# ESP32_with_USBC.net
KiCad netlist of a schematic drawn in Altium Designer
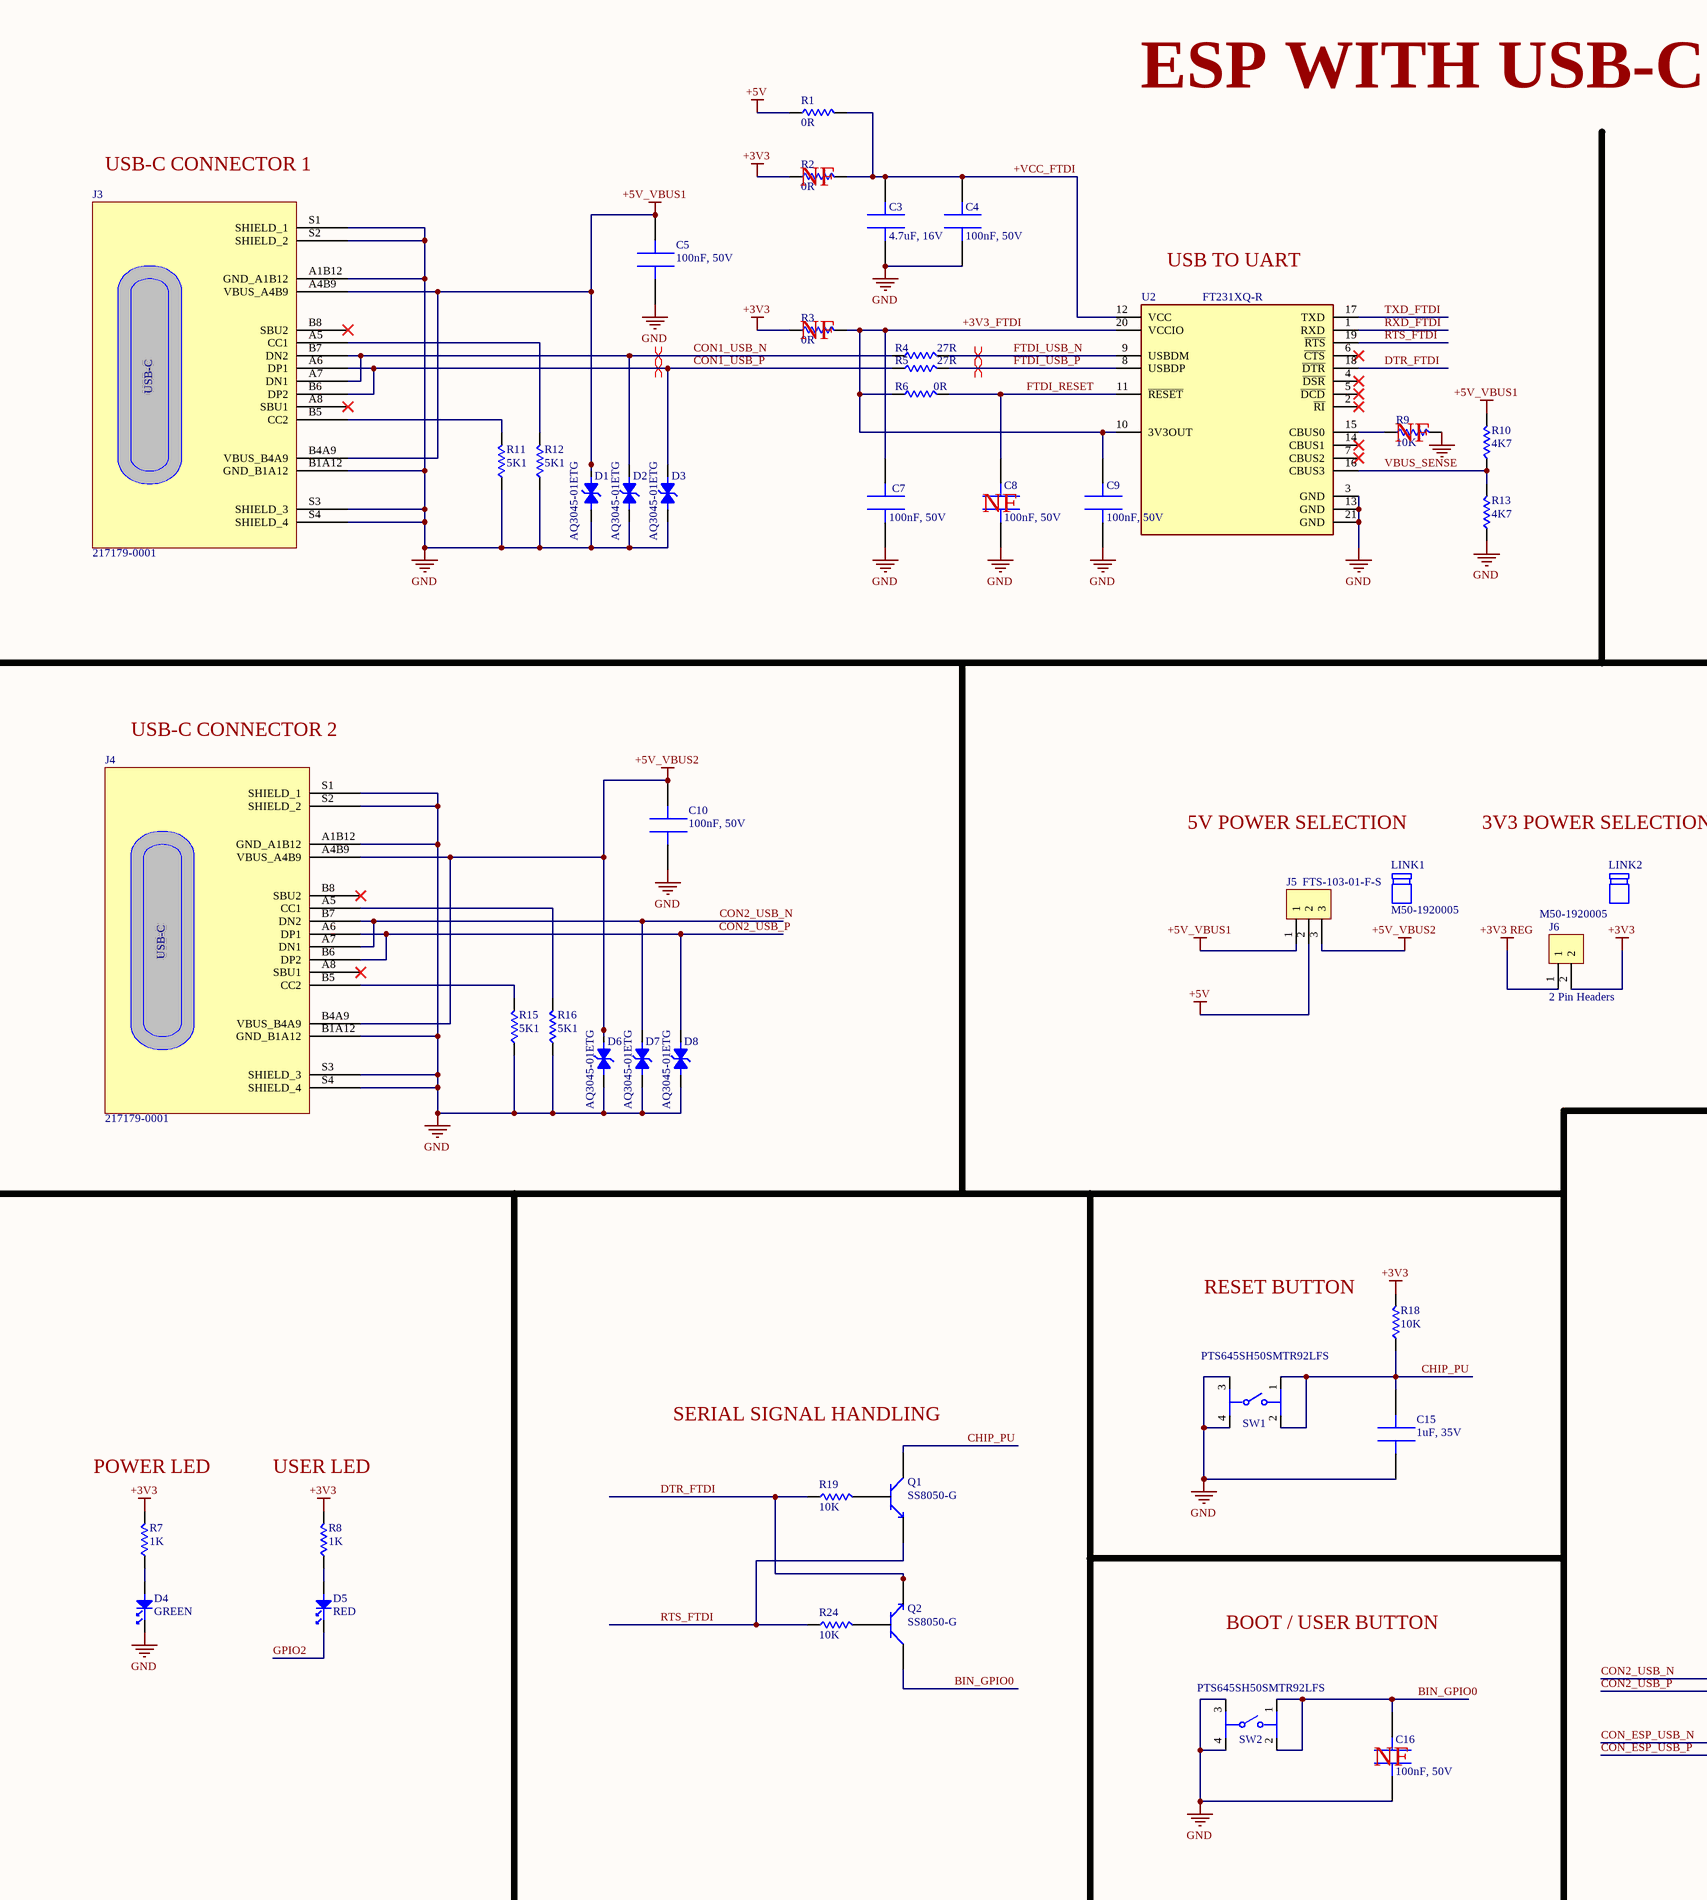
[diagram p0: ESP32 with USBC.SchDoc, left]
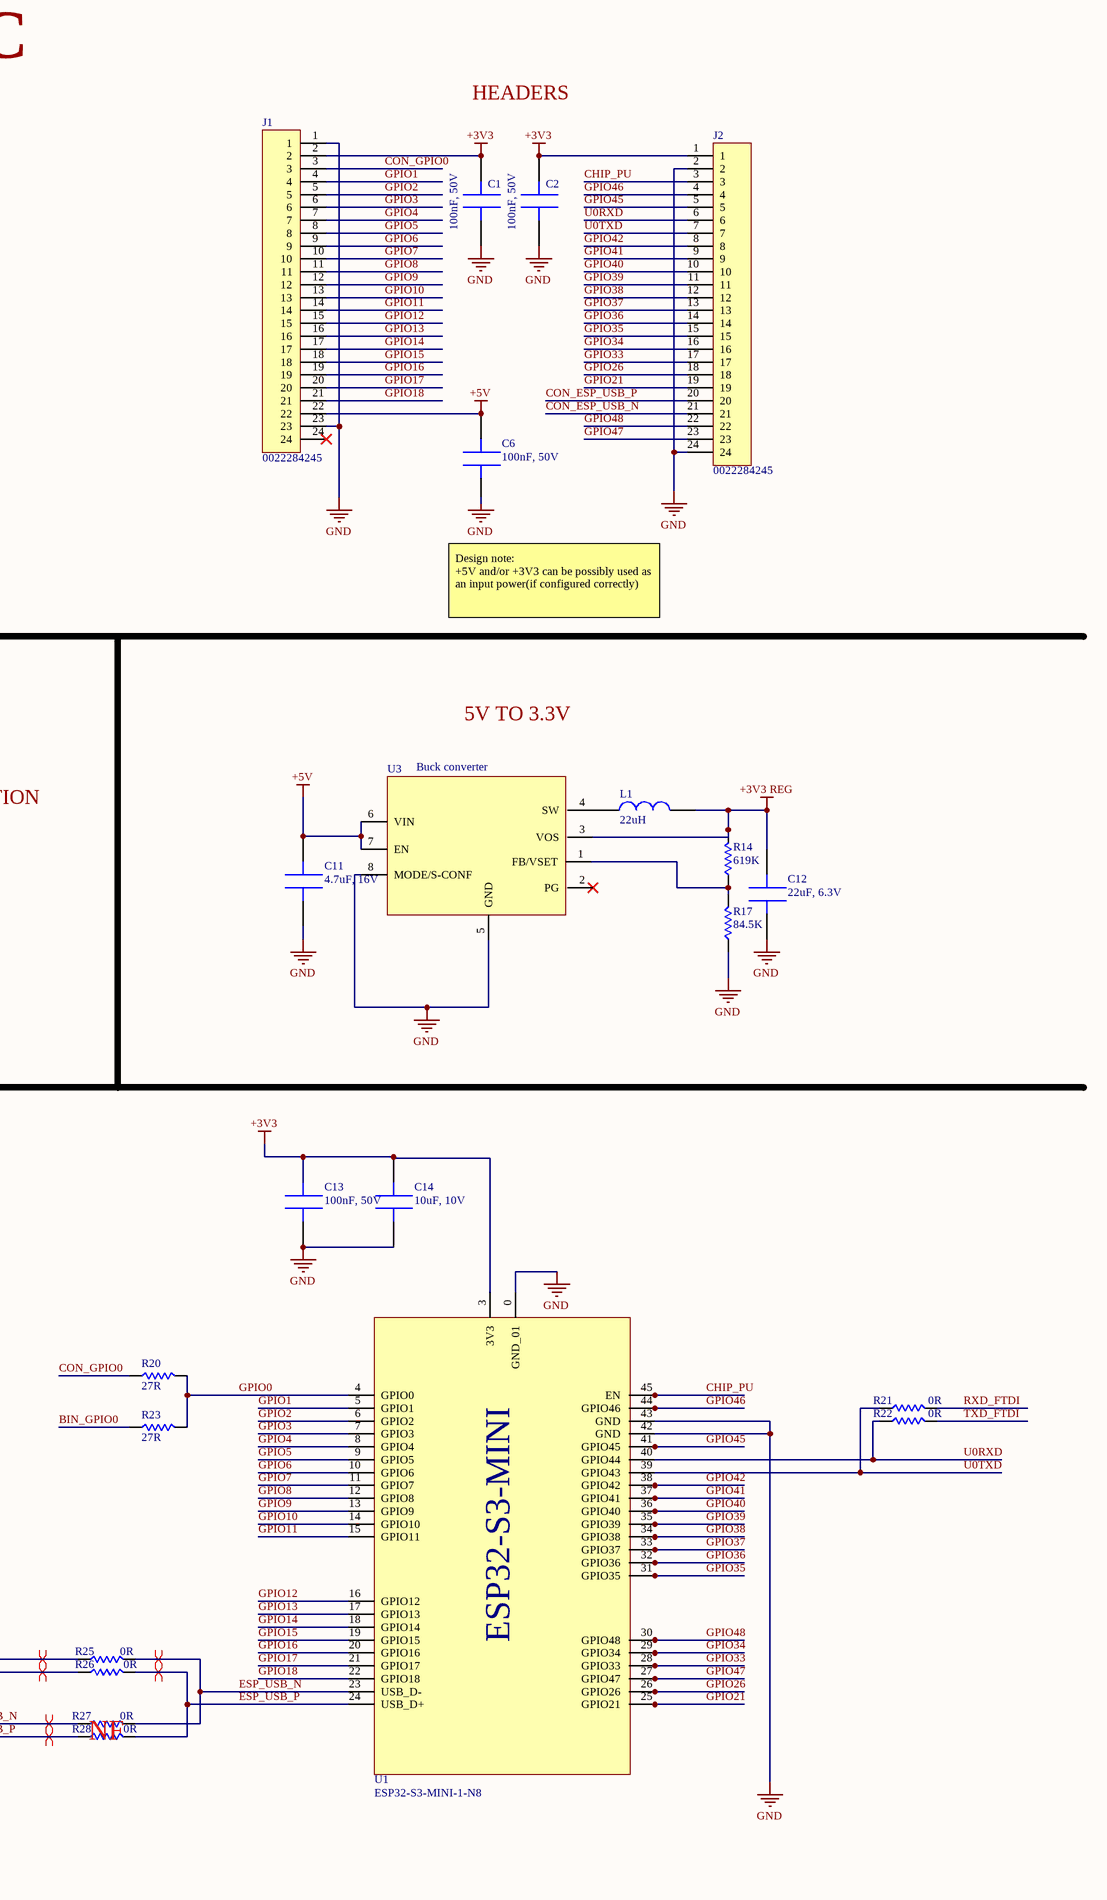
[diagram p1: ESP32 with USBC.SchDoc, right]

(export (version "E")
  (design (tool "Eeschema 10.0.6"))
  (components
    (comp (ref "C1")
      (value "100nF, 50V")
      (footprint "CAPC1005X55N")
      (description "CAP CER 0.1UF 50V X7R 0402")
      (fields
        (field (name "MANUFACTURER") "Samsung")
        (field (name "MANUFACTURER PART NUMBER") "CL05B104KB54PNC")
      )
      (libsource (lib "Schlib") (part "CL05B104KB54PNC"))
    )
    (comp (ref "C2")
      (value "100nF, 50V")
      (footprint "CAPC1005X55N")
      (description "CAP CER 0.1UF 50V X7R 0402")
      (fields
        (field (name "MANUFACTURER") "Samsung")
        (field (name "MANUFACTURER PART NUMBER") "CL05B104KB54PNC")
      )
      (libsource (lib "Schlib") (part "CL05B104KB54PNC"))
    )
    (comp (ref "C3")
      (value "4.7uF, 16V")
      (footprint "CAPC1005X55N")
      (description "16V 4.7uF X5R ±20% 0402 Multilayer Ceramic Capacitors MLCC - SMD/SMT ROHS")
      (fields
        (field (name "LCSC PART NUMBER") "C318563")
        (field (name "MANUFACTURER") "Samsung Electro-Mechanics")
      )
      (libsource (lib "Schlib") (part "CL05A475MO5NUNC"))
    )
    (comp (ref "C4")
      (value "100nF, 50V")
      (footprint "CAPC1005X55N")
      (description "CAP CER 0.1UF 50V X7R 0402")
      (fields
        (field (name "MANUFACTURER") "Samsung")
        (field (name "MANUFACTURER PART NUMBER") "CL05B104KB54PNC")
      )
      (libsource (lib "Schlib") (part "CL05B104KB54PNC"))
    )
    (comp (ref "C5")
      (value "100nF, 50V")
      (footprint "CAPC1005X55N")
      (description "CAP CER 0.1UF 50V X7R 0402")
      (fields
        (field (name "MANUFACTURER") "Samsung")
        (field (name "MANUFACTURER PART NUMBER") "CL05B104KB54PNC")
      )
      (libsource (lib "Schlib") (part "CL05B104KB54PNC"))
    )
    (comp (ref "C6")
      (value "100nF, 50V")
      (footprint "CAPC1005X55N")
      (description "CAP CER 0.1UF 50V X7R 0402")
      (fields
        (field (name "MANUFACTURER") "Samsung")
        (field (name "MANUFACTURER PART NUMBER") "CL05B104KB54PNC")
      )
      (libsource (lib "Schlib") (part "CL05B104KB54PNC"))
    )
    (comp (ref "C7")
      (value "100nF, 50V")
      (footprint "CAPC1005X55N")
      (description "CAP CER 0.1UF 50V X7R 0402")
      (fields
        (field (name "MANUFACTURER") "Samsung")
        (field (name "MANUFACTURER PART NUMBER") "CL05B104KB54PNC")
      )
      (libsource (lib "Schlib") (part "CL05B104KB54PNC"))
    )
    (comp (ref "C8")
      (value "100nF, 50V")
      (footprint "CAPC1005X55N")
      (description "CAP CER 0.1UF 50V X7R 0402")
      (fields
        (field (name "MANUFACTURER") "Samsung")
        (field (name "MANUFACTURER PART NUMBER") "CL05B104KB54PNC")
      )
      (libsource (lib "Schlib") (part "CL05B104KB54PNC"))
    )
    (comp (ref "C9")
      (value "100nF, 50V")
      (footprint "CAPC1005X55N")
      (description "CAP CER 0.1UF 50V X7R 0402")
      (fields
        (field (name "MANUFACTURER") "Samsung")
        (field (name "MANUFACTURER PART NUMBER") "CL05B104KB54PNC")
      )
      (libsource (lib "Schlib") (part "CL05B104KB54PNC"))
    )
    (comp (ref "C10")
      (value "100nF, 50V")
      (footprint "CAPC1005X55N")
      (description "CAP CER 0.1UF 50V X7R 0402")
      (fields
        (field (name "MANUFACTURER") "Samsung")
        (field (name "MANUFACTURER PART NUMBER") "CL05B104KB54PNC")
      )
      (libsource (lib "Schlib") (part "CL05B104KB54PNC"))
    )
    (comp (ref "C11")
      (value "4.7uF, 16V")
      (footprint "CAPC1005X55N")
      (description "16V 4.7uF X5R ±20% 0402 Multilayer Ceramic Capacitors MLCC - SMD/SMT ROHS")
      (fields
        (field (name "LCSC PART NUMBER") "C318563")
        (field (name "MANUFACTURER") "Samsung Electro-Mechanics")
      )
      (libsource (lib "Schlib") (part "CL05A475MO5NUNC"))
    )
    (comp (ref "C12")
      (value "22uF, 6.3V")
      (footprint "CAPC1005X55N")
      (description "6.3V 22uF X5R ±20% 0402 Multilayer Ceramic Capacitors MLCC - SMD/SMT ROHS")
      (fields
        (field (name "MANUFACTURER") "Samsung Electro-Mechanics")
        (field (name "MANUFACTURER PART NUMBER") "CL05A226MQ5QUNC")
      )
      (libsource (lib "Schlib") (part "CL05A226MQ5QUNC"))
    )
    (comp (ref "C13")
      (value "100nF, 50V")
      (footprint "CAPC1005X55N")
      (description "CAP CER 0.1UF 50V X7R 0402")
      (fields
        (field (name "MANUFACTURER") "Samsung")
        (field (name "MANUFACTURER PART NUMBER") "CL05B104KB54PNC")
      )
      (libsource (lib "Schlib") (part "CL05B104KB54PNC"))
    )
    (comp (ref "C14")
      (value "10uF, 10V")
      (footprint "CAPC1005X55N")
      (description "CAP CER 10UF 10V X5R 0402")
      (fields
        (field (name "MANUFACTURER") "Samsung")
        (field (name "MANUFACTURER PART NUMBER") "CL05A106MP8NUB8")
      )
      (libsource (lib "Schlib") (part "CL05A106MP8NUB8"))
    )
    (comp (ref "C15")
      (value "1uF, 35V")
      (footprint "CAPC1005X55N")
      (description "CAP CER 1UF 35V X5R 0402")
      (fields
        (field (name "MANUFACTURER") "Samsung")
        (field (name "MANUFACTURER PART NUMBER") "CL05A105KL5NRNC")
      )
      (libsource (lib "Schlib") (part "CL05A105KL5NRNC"))
    )
    (comp (ref "C16")
      (value "100nF, 50V")
      (footprint "CAPC1005X55N")
      (description "CAP CER 0.1UF 50V X7R 0402")
      (fields
        (field (name "MANUFACTURER") "Samsung")
        (field (name "MANUFACTURER PART NUMBER") "CL05B104KB54PNC")
      )
      (libsource (lib "Schlib") (part "CL05B104KB54PNC"))
    )
    (comp (ref "D1")
      (value "AQ3045-01ETG")
      (footprint "SOD882")
      (description "TVS DIODE 5.3VWM 12VC SOD882")
      (fields (field (name "MANUFACTURER") "Littelfuse") (field (name "LCSC PART NUMBER") "C3710326"))
      (libsource (lib "Schlib") (part "AQ3045-01ETG"))
    )
    (comp (ref "D2")
      (value "AQ3045-01ETG")
      (footprint "SOD882")
      (description "TVS DIODE 5.3VWM 12VC SOD882")
      (fields (field (name "MANUFACTURER") "Littelfuse") (field (name "LCSC PART NUMBER") "C3710326"))
      (libsource (lib "Schlib") (part "AQ3045-01ETG"))
    )
    (comp (ref "D3")
      (value "AQ3045-01ETG")
      (footprint "SOD882")
      (description "TVS DIODE 5.3VWM 12VC SOD882")
      (fields (field (name "MANUFACTURER") "Littelfuse") (field (name "LCSC PART NUMBER") "C3710326"))
      (libsource (lib "Schlib") (part "AQ3045-01ETG"))
    )
    (comp (ref "D4")
      (value "GREEN")
      (footprint "LED0402G")
      (description "20mA 35mcd 571nm Yellow Green 130° 2V 0402 LED Indication - Discrete ROHS")
      (fields
        (field (name "MANUFACTURER") "Vishay Intertech")
        (field (name "MANUFACTURER PART NUMBER") "VLMG1500-GS08")
      )
      (libsource (lib "Schlib") (part "VLMG1500-GS08"))
    )
    (comp (ref "D5")
      (value "RED")
      (footprint "LED0402R")
      (description "20mA 54mcd -30℃~+85℃ 631nm Red 130° 75mW 2V 0402 LED Indication - Discrete ROHS")
      (fields
        (field (name "MANUFACTURER") "Vishay Intertech")
        (field (name "MANUFACTURER PART NUMBER") "VLMS1500-GS08")
      )
      (libsource (lib "Schlib") (part "VLMS1500-GS08"))
    )
    (comp (ref "D6")
      (value "AQ3045-01ETG")
      (footprint "SOD882")
      (description "TVS DIODE 5.3VWM 12VC SOD882")
      (fields (field (name "MANUFACTURER") "Littelfuse") (field (name "LCSC PART NUMBER") "C3710326"))
      (libsource (lib "Schlib") (part "AQ3045-01ETG"))
    )
    (comp (ref "D7")
      (value "AQ3045-01ETG")
      (footprint "SOD882")
      (description "TVS DIODE 5.3VWM 12VC SOD882")
      (fields (field (name "MANUFACTURER") "Littelfuse") (field (name "LCSC PART NUMBER") "C3710326"))
      (libsource (lib "Schlib") (part "AQ3045-01ETG"))
    )
    (comp (ref "D8")
      (value "AQ3045-01ETG")
      (footprint "SOD882")
      (description "TVS DIODE 5.3VWM 12VC SOD882")
      (fields (field (name "MANUFACTURER") "Littelfuse") (field (name "LCSC PART NUMBER") "C3710326"))
      (libsource (lib "Schlib") (part "AQ3045-01ETG"))
    )
    (comp (ref "J1")
      (value "0022284245")
      (footprint "HDR_1X24_2.54MM")
      (description "Tin Direct Insert 24P 2.54mm Black Single Row Plugin,P=2.54mm Pin Headers ROHS")
      (fields (field (name "MANUFACTURER") "MOLEX"))
      (libsource (lib "") (part "0022284245_1"))
    )
    (comp (ref "J2")
      (value "0022284245")
      (footprint "HDR_1X24_2.54MM")
      (description "Tin Direct Insert 24P 2.54mm Black Single Row Plugin,P=2.54mm Pin Headers ROHS")
      (fields (field (name "MANUFACTURER") "MOLEX"))
      (libsource (lib "Schlib") (part "0022284245"))
    )
    (comp (ref "J3")
      (value "217179-0001")
      (footprint "FP-2171790001-MFG")
      (description "CONN RCP USB2.0 TYP C 24P SMD RA")
      (fields (field (name "MANUFACTURER") "Molex") (field (name "LCSC PART NUMBER") "C3197684"))
      (libsource (lib "Schlib") (part "217179-0001"))
    )
    (comp (ref "J4")
      (value "217179-0001")
      (footprint "FP-2171790001-MFG")
      (description "CONN RCP USB2.0 TYP C 24P SMD RA")
      (fields (field (name "MANUFACTURER") "Molex") (field (name "LCSC PART NUMBER") "C3197684"))
      (libsource (lib "Schlib") (part "217179-0001"))
    )
    (comp (ref "J5")
      (value "FTS-103-01-F-S")
      (footprint "HDR_1X3_1.27MM")
      (description "CONN HEADER VERT 3POS 1.27MM")
      (fields (field (name "MANUFACTURER") "Samtec") (field (name "LCSC PART NUMBER") "C3333578"))
      (libsource (lib "Schlib") (part "FTS-103-01-F-S"))
    )
    (comp (ref "J6")
      (value "2 Pin Headers")
      (footprint "HDR_1X2_1.27MM")
      (fields
        (field (name "MANUFACTURER") "Samtec")
        (field (name "MANUFACTURER PART NUMBER") "FTS-102-01-F-S")
      )
      (libsource (lib "Schlib") (part "FTS-102-01-F-S"))
    )
    (comp (ref "L1")
      (value "22uH")
      (footprint "Inductor")
      (description "1.04A 22uH ±10% 2.05A 238mΩ SMD,5x5.6mm Inductors (SMD) ROHS")
      (fields (field (name "MANUFACTURER") "TDK") (field (name "MANUFACTURER PART NUMBER") "B82442T1223K050"))
      (libsource (lib "Schlib") (part "B82442T1223K050"))
    )
    (comp (ref "LINK1")
      (value "M50-1920005")
      (description "CONN SHUNT 1.27MM RED")
      (fields (field (name "MANUFACTURER") "Harwin") (field (name "LCSC PART NUMBER") "C6985646"))
      (libsource (lib "Schlib") (part "M50-1920005"))
    )
    (comp (ref "LINK2")
      (value "M50-1920005")
      (description "CONN SHUNT 1.27MM RED")
      (fields (field (name "MANUFACTURER") "Harwin") (field (name "LCSC PART NUMBER") "C6985646"))
      (libsource (lib "Schlib") (part "M50-1920005"))
    )
    (comp (ref "Q1")
      (value "SS8050-G")
      (footprint "FP-SS8050-G-IPC_B")
      (description "25V 300mW 120@100mA,1V 1.5A NPN SOT-23 Bipolar (BJT) ROHS")
      (fields
        (field (name "MANUFACTURER") "Jiangsu Changjing Electronics Technology Co., Ltd.")
        (field (name "MANUFACTURER PART NUMBER") "SS8050-G(RANGE:120-200)")
      )
      (libsource (lib "Schlib") (part "SS8050-G"))
    )
    (comp (ref "Q2")
      (value "SS8050-G")
      (footprint "FP-SS8050-G-IPC_B")
      (description "25V 300mW 120@100mA,1V 1.5A NPN SOT-23 Bipolar (BJT) ROHS")
      (fields
        (field (name "MANUFACTURER") "Jiangsu Changjing Electronics Technology Co., Ltd.")
        (field (name "MANUFACTURER PART NUMBER") "SS8050-G(RANGE:120-200)")
      )
      (libsource (lib "Schlib") (part "SS8050-G"))
    )
    (comp (ref "R1")
      (value "0R")
      (footprint "RESC1005X37N")
      (description "62.5mW Thick Film Resistors 50V ±5% 0Ω 0402 Chip Resistor - Surface Mount ROHS")
      (fields
        (field (name "MANUFACTURER") "YAGEO")
        (field (name "MANUFACTURER PART NUMBER") "RC0402JR-070RL")
      )
      (libsource (lib "Schlib") (part "RC0402JR-070RL"))
    )
    (comp (ref "R2")
      (value "0R")
      (footprint "RESC1005X37N")
      (description "62.5mW Thick Film Resistors 50V ±5% 0Ω 0402 Chip Resistor - Surface Mount ROHS")
      (fields
        (field (name "MANUFACTURER") "YAGEO")
        (field (name "MANUFACTURER PART NUMBER") "RC0402JR-070RL")
      )
      (libsource (lib "Schlib") (part "RC0402JR-070RL"))
    )
    (comp (ref "R3")
      (value "0R")
      (footprint "RESC1005X37N")
      (description "62.5mW Thick Film Resistors 50V ±5% 0Ω 0402 Chip Resistor - Surface Mount ROHS")
      (fields
        (field (name "MANUFACTURER") "YAGEO")
        (field (name "MANUFACTURER PART NUMBER") "RC0402JR-070RL")
      )
      (libsource (lib "Schlib") (part "RC0402JR-070RL"))
    )
    (comp (ref "R4")
      (value "27R")
      (footprint "RESC1005X37N")
      (description "RES 27 OHM 1% 1/16W 0402")
      (fields
        (field (name "MANUFACTURER") "Yageo")
        (field (name "MANUFACTURER PART NUMBER") "RC0402FR-0727RL")
      )
      (libsource (lib "Schlib") (part "RC0402FR-0727RL"))
    )
    (comp (ref "R5")
      (value "27R")
      (footprint "RESC1005X37N")
      (description "RES 27 OHM 1% 1/16W 0402")
      (fields
        (field (name "MANUFACTURER") "Yageo")
        (field (name "MANUFACTURER PART NUMBER") "RC0402FR-0727RL")
      )
      (libsource (lib "Schlib") (part "RC0402FR-0727RL"))
    )
    (comp (ref "R6")
      (value "0R")
      (footprint "RESC1005X37N")
      (description "62.5mW Thick Film Resistors 50V ±5% 0Ω 0402 Chip Resistor - Surface Mount ROHS")
      (fields
        (field (name "MANUFACTURER") "YAGEO")
        (field (name "MANUFACTURER PART NUMBER") "RC0402JR-070RL")
      )
      (libsource (lib "Schlib") (part "RC0402JR-070RL"))
    )
    (comp (ref "R7")
      (value "1K")
      (footprint "RESC1005X37N")
      (description "62.5mW Thick Film Resistors 50V ±100ppm/℃ ±1% 1kΩ 0402 Chip Resistor - Surface Mount ROHS")
      (fields
        (field (name "MANUFACTURER") "YAGEO")
        (field (name "MANUFACTURER PART NUMBER") "RC0402FR-071KL")
      )
      (libsource (lib "Schlib") (part "RC0402FR-071KL"))
    )
    (comp (ref "R8")
      (value "1K")
      (footprint "RESC1005X37N")
      (description "62.5mW Thick Film Resistors 50V ±100ppm/℃ ±1% 1kΩ 0402 Chip Resistor - Surface Mount ROHS")
      (fields
        (field (name "MANUFACTURER") "YAGEO")
        (field (name "MANUFACTURER PART NUMBER") "RC0402FR-071KL")
      )
      (libsource (lib "Schlib") (part "RC0402FR-071KL"))
    )
    (comp (ref "R9")
      (value "10K")
      (footprint "RESC1005X37N")
      (description "RES SMD 10K OHM 1% 1/16W 0402")
      (fields
        (field (name "MANUFACTURER") "Yageo")
        (field (name "MANUFACTURER PART NUMBER") "AC0402FR-0710KL")
      )
      (libsource (lib "Schlib") (part "AC0402FR-0710KL"))
    )
    (comp (ref "R10")
      (value "4K7")
      (footprint "RESC1005X37N")
      (description "62.5mW Thick Film Resistors 50V ±100ppm/℃ ±1% 4.7kΩ 0402 Chip Resistor - Surface Mount ROHS")
      (fields
        (field (name "MANUFACTURER") "YAGEO")
        (field (name "MANUFACTURER PART NUMBER") "RC0402FR-074K7L")
      )
      (libsource (lib "Schlib") (part "RC0402FR-074K7L"))
    )
    (comp (ref "R11")
      (value "5K1")
      (footprint "RESC1005X37N")
      (description "RES SMD 5.1K OHM 1% 1/16W 0402")
      (fields
        (field (name "MANUFACTURER") "Yageo")
        (field (name "MANUFACTURER PART NUMBER") "AC0402FR-075K1L")
      )
      (libsource (lib "Schlib") (part "AC0402FR-075K1L"))
    )
    (comp (ref "R12")
      (value "5K1")
      (footprint "RESC1005X37N")
      (description "RES SMD 5.1K OHM 1% 1/16W 0402")
      (fields
        (field (name "MANUFACTURER") "Yageo")
        (field (name "MANUFACTURER PART NUMBER") "AC0402FR-075K1L")
      )
      (libsource (lib "Schlib") (part "AC0402FR-075K1L"))
    )
    (comp (ref "R13")
      (value "4K7")
      (footprint "RESC1005X37N")
      (description "62.5mW Thick Film Resistors 50V ±100ppm/℃ ±1% 4.7kΩ 0402 Chip Resistor - Surface Mount ROHS")
      (fields
        (field (name "MANUFACTURER") "YAGEO")
        (field (name "MANUFACTURER PART NUMBER") "RC0402FR-074K7L")
      )
      (libsource (lib "Schlib") (part "RC0402FR-074K7L"))
    )
    (comp (ref "R14")
      (value "619K")
      (footprint "RESC1005X37N")
      (description "50mW Thick Film Resistors 25V ±300ppm/℃ ±1% 619kΩ 0201 Chip Resistor - Surface Mount ROHS")
      (fields
        (field (name "MANUFACTURER") "YAGEO")
        (field (name "MANUFACTURER PART NUMBER") "AA0201FR-07619KL")
      )
      (libsource (lib "Schlib") (part "RC0201FR-07124KL"))
    )
    (comp (ref "R15")
      (value "5K1")
      (footprint "RESC1005X37N")
      (description "RES SMD 5.1K OHM 1% 1/16W 0402")
      (fields
        (field (name "MANUFACTURER") "Yageo")
        (field (name "MANUFACTURER PART NUMBER") "AC0402FR-075K1L")
      )
      (libsource (lib "Schlib") (part "AC0402FR-075K1L"))
    )
    (comp (ref "R16")
      (value "5K1")
      (footprint "RESC1005X37N")
      (description "RES SMD 5.1K OHM 1% 1/16W 0402")
      (fields
        (field (name "MANUFACTURER") "Yageo")
        (field (name "MANUFACTURER PART NUMBER") "AC0402FR-075K1L")
      )
      (libsource (lib "Schlib") (part "AC0402FR-075K1L"))
    )
    (comp (ref "R17")
      (value "84.5K")
      (footprint "RESC1005X37N")
      (description "50mW Thick Film Resistors 25V ±1% ±200ppm/℃ 84.5kΩ 0201 Chip Resistor - Surface Mount ROHS")
      (fields
        (field (name "MANUFACTURER") "YAGEO")
        (field (name "MANUFACTURER PART NUMBER") "RC0201FR-0784K5L")
      )
      (libsource (lib "Schlib") (part "RC0201FR-0784K5L"))
    )
    (comp (ref "R18")
      (value "10K")
      (footprint "RESC1005X37N")
      (description "RES SMD 10K OHM 1% 1/16W 0402")
      (fields
        (field (name "MANUFACTURER") "Yageo")
        (field (name "MANUFACTURER PART NUMBER") "AC0402FR-0710KL")
      )
      (libsource (lib "Schlib") (part "AC0402FR-0710KL"))
    )
    (comp (ref "R19")
      (value "10K")
      (footprint "RESC1005X37N")
      (description "RES SMD 10K OHM 1% 1/16W 0402")
      (fields
        (field (name "MANUFACTURER") "Yageo")
        (field (name "MANUFACTURER PART NUMBER") "AC0402FR-0710KL")
      )
      (libsource (lib "Schlib") (part "AC0402FR-0710KL"))
    )
    (comp (ref "R20")
      (value "27R")
      (footprint "RESC1005X37N")
      (description "RES 27 OHM 1% 1/16W 0402")
      (fields
        (field (name "MANUFACTURER") "Yageo")
        (field (name "MANUFACTURER PART NUMBER") "RC0402FR-0727RL")
      )
      (libsource (lib "Schlib") (part "RC0402FR-0727RL"))
    )
    (comp (ref "R21")
      (value "0R")
      (footprint "RESC1005X37N")
      (description "62.5mW Thick Film Resistors 50V ±5% 0Ω 0402 Chip Resistor - Surface Mount ROHS")
      (fields
        (field (name "MANUFACTURER") "YAGEO")
        (field (name "MANUFACTURER PART NUMBER") "RC0402JR-070RL")
      )
      (libsource (lib "Schlib") (part "RC0402JR-070RL"))
    )
    (comp (ref "R22")
      (value "0R")
      (footprint "RESC1005X37N")
      (description "62.5mW Thick Film Resistors 50V ±5% 0Ω 0402 Chip Resistor - Surface Mount ROHS")
      (fields
        (field (name "MANUFACTURER") "YAGEO")
        (field (name "MANUFACTURER PART NUMBER") "RC0402JR-070RL")
      )
      (libsource (lib "Schlib") (part "RC0402JR-070RL"))
    )
    (comp (ref "R23")
      (value "27R")
      (footprint "RESC1005X37N")
      (description "RES 27 OHM 1% 1/16W 0402")
      (fields
        (field (name "MANUFACTURER") "Yageo")
        (field (name "MANUFACTURER PART NUMBER") "RC0402FR-0727RL")
      )
      (libsource (lib "Schlib") (part "RC0402FR-0727RL"))
    )
    (comp (ref "R24")
      (value "10K")
      (footprint "RESC1005X37N")
      (description "RES SMD 10K OHM 1% 1/16W 0402")
      (fields
        (field (name "MANUFACTURER") "Yageo")
        (field (name "MANUFACTURER PART NUMBER") "AC0402FR-0710KL")
      )
      (libsource (lib "Schlib") (part "AC0402FR-0710KL"))
    )
    (comp (ref "R25")
      (value "0R")
      (footprint "RESC1005X37N")
      (description "62.5mW Thick Film Resistors 50V ±5% 0Ω 0402 Chip Resistor - Surface Mount ROHS")
      (fields
        (field (name "MANUFACTURER") "YAGEO")
        (field (name "MANUFACTURER PART NUMBER") "RC0402JR-070RL")
      )
      (libsource (lib "Schlib") (part "RC0402JR-070RL"))
    )
    (comp (ref "R26")
      (value "0R")
      (footprint "RESC1005X37N")
      (description "62.5mW Thick Film Resistors 50V ±5% 0Ω 0402 Chip Resistor - Surface Mount ROHS")
      (fields
        (field (name "MANUFACTURER") "YAGEO")
        (field (name "MANUFACTURER PART NUMBER") "RC0402JR-070RL")
      )
      (libsource (lib "Schlib") (part "RC0402JR-070RL"))
    )
    (comp (ref "R27")
      (value "0R")
      (footprint "RESC1005X37N")
      (description "62.5mW Thick Film Resistors 50V ±5% 0Ω 0402 Chip Resistor - Surface Mount ROHS")
      (fields
        (field (name "MANUFACTURER") "YAGEO")
        (field (name "MANUFACTURER PART NUMBER") "RC0402JR-070RL")
      )
      (libsource (lib "Schlib") (part "RC0402JR-070RL"))
    )
    (comp (ref "R28")
      (value "0R")
      (footprint "RESC1005X37N")
      (description "62.5mW Thick Film Resistors 50V ±5% 0Ω 0402 Chip Resistor - Surface Mount ROHS")
      (fields
        (field (name "MANUFACTURER") "YAGEO")
        (field (name "MANUFACTURER PART NUMBER") "RC0402JR-070RL")
      )
      (libsource (lib "Schlib") (part "RC0402JR-070RL"))
    )
    (comp (ref "SW1")
      (value "PTS645SH50SMTR92LFS")
      (footprint "FP-PTS645SH50SMTR92LFS-MFG")
      (description "SWITCH TACTILE SPST-NO 0.05A 12V")
      (fields (field (name "MANUFACTURER") "ITT C&K") (field (name "LCSC PART NUMBER") "C221869"))
      (libsource (lib "Schlib") (part "PTS645SH50SMTR92LFS"))
    )
    (comp (ref "SW2")
      (value "PTS645SH50SMTR92LFS")
      (footprint "FP-PTS645SH50SMTR92LFS-MFG")
      (description "SWITCH TACTILE SPST-NO 0.05A 12V")
      (fields (field (name "MANUFACTURER") "ITT C&K") (field (name "LCSC PART NUMBER") "C221869"))
      (libsource (lib "Schlib") (part "PTS645SH50SMTR92LFS"))
    )
    (comp (ref "U1")
      (value "ESP32-S3-MINI-1-N8")
      (footprint "XCVR_ESP32-S3-MINI-1-N8")
      (description "SMD module, ESP32-S3FN8, 8 MB SPI flash, PCB antenna")
      (fields (field (name "MANUFACTURER") "Espressif Systems") (field (name "LCSC PART NUMBER") "C2913206"))
      (libsource (lib "Schlib") (part "ESP32-S3-MINI-1-N8"))
    )
    (comp (ref "U2")
      (value "FT231XQ-R")
      (footprint "FP-QFN-20-IPC_B")
      (description "USB to UART UART QFN-20-EP(4x4) USB Converters ROHS")
      (fields (field (name "LCSC PART NUMBER") "C132159") (field (name "MANUFACTURER") "FTDI"))
      (libsource (lib "Schlib") (part "FT231XQ-R"))
    )
    (comp (ref "U3")
      (value "Buck converter")
      (footprint "SOT50P160X60-8N")
      (description "400mV~5.5V 1A 3V~17V SOT-5x3(DRL)-8 DC-DC Converters ROHS")
      (fields (field (name "LCSC PART NUMBER") "C5219301") (field (name "MANUFACTURER") "Texas Instruments"))
      (libsource (lib "Schlib") (part "TPS629210DRLR"))
    )
  )
  (nets
    (net (code "1") (name "+3V3") (class "Default")
      (node (ref "C1") (pin "2") (pinfunction "2_2") (pintype "passive"))
      (node (ref "C13") (pin "2") (pinfunction "2_2") (pintype "passive"))
      (node (ref "C14") (pin "2") (pinfunction "2_2") (pintype "passive"))
      (node (ref "C2") (pin "2") (pinfunction "2_2") (pintype "passive"))
      (node (ref "J1") (pin "2") (pinfunction "2_2") (pintype "passive"))
      (node (ref "J2") (pin "1") (pinfunction "1_1") (pintype "passive"))
      (node (ref "J6") (pin "2") (pinfunction "2_2") (pintype "passive"))
      (node (ref "R18") (pin "2") (pinfunction "2_2") (pintype "passive"))
      (node (ref "R2") (pin "1") (pinfunction "1_1") (pintype "passive"))
      (node (ref "R3") (pin "1") (pinfunction "1_1") (pintype "passive"))
      (node (ref "R7") (pin "2") (pinfunction "2_2") (pintype "passive"))
      (node (ref "R8") (pin "2") (pinfunction "2_2") (pintype "passive"))
      (node (ref "U1") (pin "3") (pinfunction "3V3_3") (pintype "passive"))
    )
    (net (code "2") (name "+3V3 REG") (class "Default")
      (node (ref "C12") (pin "2") (pinfunction "2_2") (pintype "passive"))
      (node (ref "J6") (pin "1") (pinfunction "1_1") (pintype "passive"))
      (node (ref "L1") (pin "2") (pinfunction "2_2") (pintype "passive"))
      (node (ref "R14") (pin "2") (pinfunction "2_2") (pintype "passive"))
      (node (ref "U3") (pin "3") (pinfunction "VOS_3") (pintype "passive"))
    )
    (net (code "3") (name "+5V") (class "Default")
      (node (ref "C11") (pin "2") (pinfunction "2_2") (pintype "passive"))
      (node (ref "C6") (pin "2") (pinfunction "2_2") (pintype "passive"))
      (node (ref "J1") (pin "22") (pinfunction "22_22") (pintype "passive"))
      (node (ref "J5") (pin "2") (pinfunction "2_2") (pintype "passive"))
      (node (ref "R1") (pin "1") (pinfunction "1_1") (pintype "passive"))
      (node (ref "U3") (pin "6") (pinfunction "VIN_6") (pintype "passive"))
      (node (ref "U3") (pin "7") (pinfunction "EN_7") (pintype "passive"))
    )
    (net (code "4") (name "+5V_VBUS1") (class "Default")
      (node (ref "C5") (pin "2") (pinfunction "2_2") (pintype "passive"))
      (node (ref "D1") (pin "2") (pinfunction "2_2") (pintype "passive"))
      (node (ref "J3") (pin "A4B9") (pinfunction "VBUS_A4B9_A4B9") (pintype "passive"))
      (node (ref "J3") (pin "B4A9") (pinfunction "VBUS_B4A9_B4A9") (pintype "passive"))
      (node (ref "J5") (pin "1") (pinfunction "1_1") (pintype "passive"))
      (node (ref "R10") (pin "2") (pinfunction "2_2") (pintype "passive"))
    )
    (net (code "5") (name "+5V_VBUS2") (class "Default")
      (node (ref "C10") (pin "2") (pinfunction "2_2") (pintype "passive"))
      (node (ref "D6") (pin "2") (pinfunction "2_2") (pintype "passive"))
      (node (ref "J4") (pin "A4B9") (pinfunction "VBUS_A4B9_A4B9") (pintype "passive"))
      (node (ref "J4") (pin "B4A9") (pinfunction "VBUS_B4A9_B4A9") (pintype "passive"))
      (node (ref "J5") (pin "3") (pinfunction "3_3") (pintype "passive"))
    )
    (net (code "6") (name "/+3V3_FTDI") (class "Default")
      (node (ref "C7") (pin "2") (pinfunction "2_2") (pintype "passive"))
      (node (ref "C9") (pin "2") (pinfunction "2_2") (pintype "passive"))
      (node (ref "R3") (pin "2") (pinfunction "2_2") (pintype "passive"))
      (node (ref "R6") (pin "1") (pinfunction "1_1") (pintype "passive"))
      (node (ref "U2") (pin "10") (pinfunction "3V3OUT_10") (pintype "passive"))
      (node (ref "U2") (pin "20") (pinfunction "VCCIO_20") (pintype "passive"))
    )
    (net (code "7") (name "/+VCC_FTDI") (class "Default")
      (node (ref "C3") (pin "2") (pinfunction "2_2") (pintype "passive"))
      (node (ref "C4") (pin "2") (pinfunction "2_2") (pintype "passive"))
      (node (ref "R1") (pin "2") (pinfunction "2_2") (pintype "passive"))
      (node (ref "R2") (pin "2") (pinfunction "2_2") (pintype "passive"))
      (node (ref "U2") (pin "12") (pinfunction "VCC_12") (pintype "passive"))
    )
    (net (code "8") (name "/BIN_GPIO0") (class "Default")
      (node (ref "C16") (pin "2") (pinfunction "2_2") (pintype "passive"))
      (node (ref "Q2") (pin "3") (pinfunction "3_3") (pintype "passive"))
      (node (ref "R23") (pin "1") (pinfunction "1_1") (pintype "passive"))
      (node (ref "SW2") (pin "1") (pinfunction "1_1") (pintype "passive"))
      (node (ref "SW2") (pin "2") (pinfunction "2_2") (pintype "passive"))
    )
    (net (code "9") (name "/CHIP_PU") (class "Default")
      (node (ref "C15") (pin "2") (pinfunction "2_2") (pintype "passive"))
      (node (ref "J2") (pin "3") (pinfunction "3_3") (pintype "passive"))
      (node (ref "Q1") (pin "3") (pinfunction "3_3") (pintype "passive"))
      (node (ref "R18") (pin "1") (pinfunction "1_1") (pintype "passive"))
      (node (ref "SW1") (pin "1") (pinfunction "1_1") (pintype "passive"))
      (node (ref "SW1") (pin "2") (pinfunction "2_2") (pintype "passive"))
      (node (ref "U1") (pin "45") (pinfunction "EN_45") (pintype "passive"))
    )
    (net (code "10") (name "/CON1_USB_N") (class "Default")
      (node (ref "D2") (pin "2") (pinfunction "2_2") (pintype "passive"))
      (node (ref "J3") (pin "A7") (pinfunction "DN1_A7") (pintype "passive"))
      (node (ref "J3") (pin "B7") (pinfunction "DN2_B7") (pintype "passive"))
      (node (ref "R4") (pin "1") (pinfunction "1_1") (pintype "passive"))
    )
    (net (code "11") (name "/CON1_USB_P") (class "Default")
      (node (ref "D3") (pin "2") (pinfunction "2_2") (pintype "passive"))
      (node (ref "J3") (pin "A6") (pinfunction "DP1_A6") (pintype "passive"))
      (node (ref "J3") (pin "B6") (pinfunction "DP2_B6") (pintype "passive"))
      (node (ref "R5") (pin "1") (pinfunction "1_1") (pintype "passive"))
    )
    (net (code "12") (name "/CON2_USB_N") (class "Default")
      (node (ref "D7") (pin "2") (pinfunction "2_2") (pintype "passive"))
      (node (ref "J4") (pin "A7") (pinfunction "DN1_A7") (pintype "passive"))
      (node (ref "J4") (pin "B7") (pinfunction "DN2_B7") (pintype "passive"))
      (node (ref "R25") (pin "1") (pinfunction "1_1") (pintype "passive"))
    )
    (net (code "13") (name "/CON2_USB_P") (class "Default")
      (node (ref "D8") (pin "2") (pinfunction "2_2") (pintype "passive"))
      (node (ref "J4") (pin "A6") (pinfunction "DP1_A6") (pintype "passive"))
      (node (ref "J4") (pin "B6") (pinfunction "DP2_B6") (pintype "passive"))
      (node (ref "R26") (pin "1") (pinfunction "1_1") (pintype "passive"))
    )
    (net (code "14") (name "/CON_ESP_USB_N") (class "Default")
      (node (ref "J2") (pin "21") (pinfunction "21_21") (pintype "passive"))
      (node (ref "R27") (pin "1") (pinfunction "1_1") (pintype "passive"))
    )
    (net (code "15") (name "/CON_ESP_USB_P") (class "Default")
      (node (ref "J2") (pin "20") (pinfunction "20_20") (pintype "passive"))
      (node (ref "R28") (pin "1") (pinfunction "1_1") (pintype "passive"))
    )
    (net (code "16") (name "/CON_GPIO0") (class "Default")
      (node (ref "J1") (pin "3") (pinfunction "3_3") (pintype "passive"))
      (node (ref "R20") (pin "1") (pinfunction "1_1") (pintype "passive"))
    )
    (net (code "17") (name "/DTR_FTDI") (class "Default")
      (node (ref "Q2") (pin "2") (pinfunction "2_2") (pintype "passive"))
      (node (ref "R19") (pin "1") (pinfunction "1_1") (pintype "passive"))
      (node (ref "U2") (pin "18") (pinfunction "~{DTR}_18") (pintype "passive"))
    )
    (net (code "18") (name "/ESP_USB_N") (class "Default")
      (node (ref "R25") (pin "2") (pinfunction "2_2") (pintype "passive"))
      (node (ref "R27") (pin "2") (pinfunction "2_2") (pintype "passive"))
      (node (ref "U1") (pin "23") (pinfunction "USB_D-_23") (pintype "passive"))
    )
    (net (code "19") (name "/ESP_USB_P") (class "Default")
      (node (ref "R26") (pin "2") (pinfunction "2_2") (pintype "passive"))
      (node (ref "R28") (pin "2") (pinfunction "2_2") (pintype "passive"))
      (node (ref "U1") (pin "24") (pinfunction "USB_D+_24") (pintype "passive"))
    )
    (net (code "20") (name "/FTDI_RESET") (class "Default")
      (node (ref "C8") (pin "2") (pinfunction "2_2") (pintype "passive"))
      (node (ref "R6") (pin "2") (pinfunction "2_2") (pintype "passive"))
      (node (ref "U2") (pin "11") (pinfunction "~{RESET}_11") (pintype "passive"))
    )
    (net (code "21") (name "/FTDI_USB_N") (class "Default")
      (node (ref "R4") (pin "2") (pinfunction "2_2") (pintype "passive"))
      (node (ref "U2") (pin "9") (pinfunction "USBDM_9") (pintype "passive"))
    )
    (net (code "22") (name "/FTDI_USB_P") (class "Default")
      (node (ref "R5") (pin "2") (pinfunction "2_2") (pintype "passive"))
      (node (ref "U2") (pin "8") (pinfunction "USBDP_8") (pintype "passive"))
    )
    (net (code "23") (name "/GPIO0") (class "Default")
      (node (ref "R20") (pin "2") (pinfunction "2_2") (pintype "passive"))
      (node (ref "R23") (pin "2") (pinfunction "2_2") (pintype "passive"))
      (node (ref "U1") (pin "4") (pinfunction "GPIO0_4") (pintype "passive"))
    )
    (net (code "24") (name "/GPIO1") (class "Default")
      (node (ref "J1") (pin "4") (pinfunction "4_4") (pintype "passive"))
      (node (ref "U1") (pin "5") (pinfunction "GPIO1_5") (pintype "passive"))
    )
    (net (code "25") (name "/GPIO2") (class "Default")
      (node (ref "D5") (pin "1") (pinfunction "1_1") (pintype "passive"))
      (node (ref "J1") (pin "5") (pinfunction "5_5") (pintype "passive"))
      (node (ref "U1") (pin "6") (pinfunction "GPIO2_6") (pintype "passive"))
    )
    (net (code "26") (name "/GPIO3") (class "Default")
      (node (ref "J1") (pin "6") (pinfunction "6_6") (pintype "passive"))
      (node (ref "U1") (pin "7") (pinfunction "GPIO3_7") (pintype "passive"))
    )
    (net (code "27") (name "/GPIO4") (class "Default")
      (node (ref "J1") (pin "7") (pinfunction "7_7") (pintype "passive"))
      (node (ref "U1") (pin "8") (pinfunction "GPIO4_8") (pintype "passive"))
    )
    (net (code "28") (name "/GPIO5") (class "Default")
      (node (ref "J1") (pin "8") (pinfunction "8_8") (pintype "passive"))
      (node (ref "U1") (pin "9") (pinfunction "GPIO5_9") (pintype "passive"))
    )
    (net (code "29") (name "/GPIO6") (class "Default")
      (node (ref "J1") (pin "9") (pinfunction "9_9") (pintype "passive"))
      (node (ref "U1") (pin "10") (pinfunction "GPIO6_10") (pintype "passive"))
    )
    (net (code "30") (name "/GPIO7") (class "Default")
      (node (ref "J1") (pin "10") (pinfunction "10_10") (pintype "passive"))
      (node (ref "U1") (pin "11") (pinfunction "GPIO7_11") (pintype "passive"))
    )
    (net (code "31") (name "/GPIO8") (class "Default")
      (node (ref "J1") (pin "11") (pinfunction "11_11") (pintype "passive"))
      (node (ref "U1") (pin "12") (pinfunction "GPIO8_12") (pintype "passive"))
    )
    (net (code "32") (name "/GPIO9") (class "Default")
      (node (ref "J1") (pin "12") (pinfunction "12_12") (pintype "passive"))
      (node (ref "U1") (pin "13") (pinfunction "GPIO9_13") (pintype "passive"))
    )
    (net (code "33") (name "/GPIO10") (class "Default")
      (node (ref "J1") (pin "13") (pinfunction "13_13") (pintype "passive"))
      (node (ref "U1") (pin "14") (pinfunction "GPIO10_14") (pintype "passive"))
    )
    (net (code "34") (name "/GPIO11") (class "Default")
      (node (ref "J1") (pin "14") (pinfunction "14_14") (pintype "passive"))
      (node (ref "U1") (pin "15") (pinfunction "GPIO11_15") (pintype "passive"))
    )
    (net (code "35") (name "/GPIO12") (class "Default")
      (node (ref "J1") (pin "15") (pinfunction "15_15") (pintype "passive"))
      (node (ref "U1") (pin "16") (pinfunction "GPIO12_16") (pintype "passive"))
    )
    (net (code "36") (name "/GPIO13") (class "Default")
      (node (ref "J1") (pin "16") (pinfunction "16_16") (pintype "passive"))
      (node (ref "U1") (pin "17") (pinfunction "GPIO13_17") (pintype "passive"))
    )
    (net (code "37") (name "/GPIO14") (class "Default")
      (node (ref "J1") (pin "17") (pinfunction "17_17") (pintype "passive"))
      (node (ref "U1") (pin "18") (pinfunction "GPIO14_18") (pintype "passive"))
    )
    (net (code "38") (name "/GPIO15") (class "Default")
      (node (ref "J1") (pin "18") (pinfunction "18_18") (pintype "passive"))
      (node (ref "U1") (pin "19") (pinfunction "GPIO15_19") (pintype "passive"))
    )
    (net (code "39") (name "/GPIO16") (class "Default")
      (node (ref "J1") (pin "19") (pinfunction "19_19") (pintype "passive"))
      (node (ref "U1") (pin "20") (pinfunction "GPIO16_20") (pintype "passive"))
    )
    (net (code "40") (name "/GPIO17") (class "Default")
      (node (ref "J1") (pin "20") (pinfunction "20_20") (pintype "passive"))
      (node (ref "U1") (pin "21") (pinfunction "GPIO17_21") (pintype "passive"))
    )
    (net (code "41") (name "/GPIO18") (class "Default")
      (node (ref "J1") (pin "21") (pinfunction "21_21") (pintype "passive"))
      (node (ref "U1") (pin "22") (pinfunction "GPIO18_22") (pintype "passive"))
    )
    (net (code "42") (name "/GPIO21") (class "Default")
      (node (ref "J2") (pin "19") (pinfunction "19_19") (pintype "passive"))
      (node (ref "U1") (pin "25") (pinfunction "GPIO21_25") (pintype "passive"))
    )
    (net (code "43") (name "/GPIO26") (class "Default")
      (node (ref "J2") (pin "18") (pinfunction "18_18") (pintype "passive"))
      (node (ref "U1") (pin "26") (pinfunction "GPIO26_26") (pintype "passive"))
    )
    (net (code "44") (name "/GPIO33") (class "Default")
      (node (ref "J2") (pin "17") (pinfunction "17_17") (pintype "passive"))
      (node (ref "U1") (pin "28") (pinfunction "GPIO33_28") (pintype "passive"))
    )
    (net (code "45") (name "/GPIO34") (class "Default")
      (node (ref "J2") (pin "16") (pinfunction "16_16") (pintype "passive"))
      (node (ref "U1") (pin "29") (pinfunction "GPIO34_29") (pintype "passive"))
    )
    (net (code "46") (name "/GPIO35") (class "Default")
      (node (ref "J2") (pin "15") (pinfunction "15_15") (pintype "passive"))
      (node (ref "U1") (pin "31") (pinfunction "GPIO35_31") (pintype "passive"))
    )
    (net (code "47") (name "/GPIO36") (class "Default")
      (node (ref "J2") (pin "14") (pinfunction "14_14") (pintype "passive"))
      (node (ref "U1") (pin "32") (pinfunction "GPIO36_32") (pintype "passive"))
    )
    (net (code "48") (name "/GPIO37") (class "Default")
      (node (ref "J2") (pin "13") (pinfunction "13_13") (pintype "passive"))
      (node (ref "U1") (pin "33") (pinfunction "GPIO37_33") (pintype "passive"))
    )
    (net (code "49") (name "/GPIO38") (class "Default")
      (node (ref "J2") (pin "12") (pinfunction "12_12") (pintype "passive"))
      (node (ref "U1") (pin "34") (pinfunction "GPIO38_34") (pintype "passive"))
    )
    (net (code "50") (name "/GPIO39") (class "Default")
      (node (ref "J2") (pin "11") (pinfunction "11_11") (pintype "passive"))
      (node (ref "U1") (pin "35") (pinfunction "GPIO39_35") (pintype "passive"))
    )
    (net (code "51") (name "/GPIO40") (class "Default")
      (node (ref "J2") (pin "10") (pinfunction "10_10") (pintype "passive"))
      (node (ref "U1") (pin "36") (pinfunction "GPIO40_36") (pintype "passive"))
    )
    (net (code "52") (name "/GPIO41") (class "Default")
      (node (ref "J2") (pin "9") (pinfunction "9_9") (pintype "passive"))
      (node (ref "U1") (pin "37") (pinfunction "GPIO41_37") (pintype "passive"))
    )
    (net (code "53") (name "/GPIO42") (class "Default")
      (node (ref "J2") (pin "8") (pinfunction "8_8") (pintype "passive"))
      (node (ref "U1") (pin "38") (pinfunction "GPIO42_38") (pintype "passive"))
    )
    (net (code "54") (name "/GPIO45") (class "Default")
      (node (ref "J2") (pin "5") (pinfunction "5_5") (pintype "passive"))
      (node (ref "U1") (pin "41") (pinfunction "GPIO45_41") (pintype "passive"))
    )
    (net (code "55") (name "/GPIO46") (class "Default")
      (node (ref "J2") (pin "4") (pinfunction "4_4") (pintype "passive"))
      (node (ref "U1") (pin "44") (pinfunction "GPIO46_44") (pintype "passive"))
    )
    (net (code "56") (name "/GPIO47") (class "Default")
      (node (ref "J2") (pin "23") (pinfunction "23_23") (pintype "passive"))
      (node (ref "U1") (pin "27") (pinfunction "GPIO47_27") (pintype "passive"))
    )
    (net (code "57") (name "/GPIO48") (class "Default")
      (node (ref "J2") (pin "22") (pinfunction "22_22") (pintype "passive"))
      (node (ref "U1") (pin "30") (pinfunction "GPIO48_30") (pintype "passive"))
    )
    (net (code "58") (name "/RTS_FTDI") (class "Default")
      (node (ref "Q1") (pin "2") (pinfunction "2_2") (pintype "passive"))
      (node (ref "R24") (pin "1") (pinfunction "1_1") (pintype "passive"))
      (node (ref "U2") (pin "19") (pinfunction "~{RTS}_19") (pintype "passive"))
    )
    (net (code "59") (name "/RXD_FTDI") (class "Default")
      (node (ref "R21") (pin "2") (pinfunction "2_2") (pintype "passive"))
      (node (ref "U2") (pin "1") (pinfunction "RXD_1") (pintype "passive"))
    )
    (net (code "60") (name "/TXD_FTDI") (class "Default")
      (node (ref "R22") (pin "2") (pinfunction "2_2") (pintype "passive"))
      (node (ref "U2") (pin "17") (pinfunction "TXD_17") (pintype "passive"))
    )
    (net (code "61") (name "/U0RXD") (class "Default")
      (node (ref "J2") (pin "6") (pinfunction "6_6") (pintype "passive"))
      (node (ref "R22") (pin "1") (pinfunction "1_1") (pintype "passive"))
      (node (ref "U1") (pin "40") (pinfunction "GPIO44_40") (pintype "passive"))
    )
    (net (code "62") (name "/U0TXD") (class "Default")
      (node (ref "J2") (pin "7") (pinfunction "7_7") (pintype "passive"))
      (node (ref "R21") (pin "1") (pinfunction "1_1") (pintype "passive"))
      (node (ref "U1") (pin "39") (pinfunction "GPIO43_39") (pintype "passive"))
    )
    (net (code "63") (name "/VBUS_SENSE") (class "Default")
      (node (ref "R10") (pin "1") (pinfunction "1_1") (pintype "passive"))
      (node (ref "R13") (pin "2") (pinfunction "2_2") (pintype "passive"))
      (node (ref "U2") (pin "16") (pinfunction "CBUS3_16") (pintype "passive"))
    )
    (net (code "64") (name "GND") (class "Default")
      (node (ref "C1") (pin "1") (pinfunction "1_1") (pintype "passive"))
      (node (ref "C10") (pin "1") (pinfunction "1_1") (pintype "passive"))
      (node (ref "C11") (pin "1") (pinfunction "1_1") (pintype "passive"))
      (node (ref "C12") (pin "1") (pinfunction "1_1") (pintype "passive"))
      (node (ref "C13") (pin "1") (pinfunction "1_1") (pintype "passive"))
      (node (ref "C14") (pin "1") (pinfunction "1_1") (pintype "passive"))
      (node (ref "C15") (pin "1") (pinfunction "1_1") (pintype "passive"))
      (node (ref "C16") (pin "1") (pinfunction "1_1") (pintype "passive"))
      (node (ref "C2") (pin "1") (pinfunction "1_1") (pintype "passive"))
      (node (ref "C3") (pin "1") (pinfunction "1_1") (pintype "passive"))
      (node (ref "C4") (pin "1") (pinfunction "1_1") (pintype "passive"))
      (node (ref "C5") (pin "1") (pinfunction "1_1") (pintype "passive"))
      (node (ref "C6") (pin "1") (pinfunction "1_1") (pintype "passive"))
      (node (ref "C7") (pin "1") (pinfunction "1_1") (pintype "passive"))
      (node (ref "C8") (pin "1") (pinfunction "1_1") (pintype "passive"))
      (node (ref "C9") (pin "1") (pinfunction "1_1") (pintype "passive"))
      (node (ref "D1") (pin "1") (pinfunction "1_1") (pintype "passive"))
      (node (ref "D2") (pin "1") (pinfunction "1_1") (pintype "passive"))
      (node (ref "D3") (pin "1") (pinfunction "1_1") (pintype "passive"))
      (node (ref "D4") (pin "1") (pinfunction "1_1") (pintype "passive"))
      (node (ref "D6") (pin "1") (pinfunction "1_1") (pintype "passive"))
      (node (ref "D7") (pin "1") (pinfunction "1_1") (pintype "passive"))
      (node (ref "D8") (pin "1") (pinfunction "1_1") (pintype "passive"))
      (node (ref "J1") (pin "1") (pinfunction "1_1") (pintype "passive"))
      (node (ref "J1") (pin "23") (pinfunction "23_23") (pintype "passive"))
      (node (ref "J2") (pin "2") (pinfunction "2_2") (pintype "passive"))
      (node (ref "J2") (pin "24") (pinfunction "24_24") (pintype "passive"))
      (node (ref "J3") (pin "A1B12") (pinfunction "GND_A1B12_A1B12") (pintype "passive"))
      (node (ref "J3") (pin "B1A12") (pinfunction "GND_B1A12_B1A12") (pintype "passive"))
      (node (ref "J3") (pin "S1") (pinfunction "SHIELD_1_S1") (pintype "passive"))
      (node (ref "J3") (pin "S2") (pinfunction "SHIELD_2_S2") (pintype "passive"))
      (node (ref "J3") (pin "S3") (pinfunction "SHIELD_3_S3") (pintype "passive"))
      (node (ref "J3") (pin "S4") (pinfunction "SHIELD_4_S4") (pintype "passive"))
      (node (ref "J4") (pin "A1B12") (pinfunction "GND_A1B12_A1B12") (pintype "passive"))
      (node (ref "J4") (pin "B1A12") (pinfunction "GND_B1A12_B1A12") (pintype "passive"))
      (node (ref "J4") (pin "S1") (pinfunction "SHIELD_1_S1") (pintype "passive"))
      (node (ref "J4") (pin "S2") (pinfunction "SHIELD_2_S2") (pintype "passive"))
      (node (ref "J4") (pin "S3") (pinfunction "SHIELD_3_S3") (pintype "passive"))
      (node (ref "J4") (pin "S4") (pinfunction "SHIELD_4_S4") (pintype "passive"))
      (node (ref "R11") (pin "1") (pinfunction "1_1") (pintype "passive"))
      (node (ref "R12") (pin "1") (pinfunction "1_1") (pintype "passive"))
      (node (ref "R13") (pin "1") (pinfunction "1_1") (pintype "passive"))
      (node (ref "R15") (pin "1") (pinfunction "1_1") (pintype "passive"))
      (node (ref "R16") (pin "1") (pinfunction "1_1") (pintype "passive"))
      (node (ref "R17") (pin "1") (pinfunction "1_1") (pintype "passive"))
      (node (ref "R9") (pin "2") (pinfunction "2_2") (pintype "passive"))
      (node (ref "SW1") (pin "3") (pinfunction "3_3") (pintype "passive"))
      (node (ref "SW1") (pin "4") (pinfunction "4_4") (pintype "passive"))
      (node (ref "SW2") (pin "3") (pinfunction "3_3") (pintype "passive"))
      (node (ref "SW2") (pin "4") (pinfunction "4_4") (pintype "passive"))
      (node (ref "U1") (pin "0") (pinfunction "GND_01_0") (pintype "passive"))
      (node (ref "U1") (pin "42") (pinfunction "GND_42") (pintype "passive"))
      (node (ref "U1") (pin "43") (pinfunction "GND_43") (pintype "passive"))
      (node (ref "U2") (pin "13") (pinfunction "GND_13") (pintype "passive"))
      (node (ref "U2") (pin "21") (pinfunction "GND_21") (pintype "passive"))
      (node (ref "U2") (pin "3") (pinfunction "GND_3") (pintype "passive"))
      (node (ref "U3") (pin "5") (pinfunction "GND_5") (pintype "passive"))
      (node (ref "U3") (pin "8") (pinfunction "MODE/S-CONF_8") (pintype "passive"))
    )
    (net (code "65") (name "Net-(D4-Pad2)") (class "Default")
      (node (ref "D4") (pin "2") (pinfunction "2_2") (pintype "passive"))
      (node (ref "R7") (pin "1") (pinfunction "1_1") (pintype "passive"))
    )
    (net (code "66") (name "Net-(D5-Pad2)") (class "Default")
      (node (ref "D5") (pin "2") (pinfunction "2_2") (pintype "passive"))
      (node (ref "R8") (pin "1") (pinfunction "1_1") (pintype "passive"))
    )
    (net (code "67") (name "Net-(J3-CC1)") (class "Default")
      (node (ref "J3") (pin "A5") (pinfunction "CC1_A5") (pintype "passive"))
      (node (ref "R12") (pin "2") (pinfunction "2_2") (pintype "passive"))
    )
    (net (code "68") (name "Net-(J3-CC2)") (class "Default")
      (node (ref "J3") (pin "B5") (pinfunction "CC2_B5") (pintype "passive"))
      (node (ref "R11") (pin "2") (pinfunction "2_2") (pintype "passive"))
    )
    (net (code "69") (name "Net-(J4-CC1)") (class "Default")
      (node (ref "J4") (pin "A5") (pinfunction "CC1_A5") (pintype "passive"))
      (node (ref "R16") (pin "2") (pinfunction "2_2") (pintype "passive"))
    )
    (net (code "70") (name "Net-(J4-CC2)") (class "Default")
      (node (ref "J4") (pin "B5") (pinfunction "CC2_B5") (pintype "passive"))
      (node (ref "R15") (pin "2") (pinfunction "2_2") (pintype "passive"))
    )
    (net (code "71") (name "Net-(Q1-Pad1)") (class "Default")
      (node (ref "Q1") (pin "1") (pinfunction "1_1") (pintype "passive"))
      (node (ref "R19") (pin "2") (pinfunction "2_2") (pintype "passive"))
    )
    (net (code "72") (name "Net-(Q2-Pad1)") (class "Default")
      (node (ref "Q2") (pin "1") (pinfunction "1_1") (pintype "passive"))
      (node (ref "R24") (pin "2") (pinfunction "2_2") (pintype "passive"))
    )
    (net (code "73") (name "Net-(U2-CBUS0)") (class "Default")
      (node (ref "R9") (pin "1") (pinfunction "1_1") (pintype "passive"))
      (node (ref "U2") (pin "15") (pinfunction "CBUS0_15") (pintype "passive"))
    )
    (net (code "74") (name "Net-(U3-FB{slash}VSET)") (class "Default")
      (node (ref "R14") (pin "1") (pinfunction "1_1") (pintype "passive"))
      (node (ref "R17") (pin "2") (pinfunction "2_2") (pintype "passive"))
      (node (ref "U3") (pin "1") (pinfunction "FB/VSET_1") (pintype "passive"))
    )
    (net (code "75") (name "Net-(U3-SW)") (class "Default")
      (node (ref "L1") (pin "1") (pinfunction "1_1") (pintype "passive"))
      (node (ref "U3") (pin "4") (pinfunction "SW_4") (pintype "passive"))
    )
    (net (code "76") (name "unconnected-(J1-Pad24)") (class "Default")
      (node (ref "J1") (pin "24") (pinfunction "24_24") (pintype "passive+no_connect"))
    )
    (net (code "77") (name "unconnected-(J3-SBU1-PadA8)") (class "Default")
      (node (ref "J3") (pin "A8") (pinfunction "SBU1_A8") (pintype "passive+no_connect"))
    )
    (net (code "78") (name "unconnected-(J3-SBU2-PadB8)") (class "Default")
      (node (ref "J3") (pin "B8") (pinfunction "SBU2_B8") (pintype "passive+no_connect"))
    )
    (net (code "79") (name "unconnected-(J4-SBU1-PadA8)") (class "Default")
      (node (ref "J4") (pin "A8") (pinfunction "SBU1_A8") (pintype "passive+no_connect"))
    )
    (net (code "80") (name "unconnected-(J4-SBU2-PadB8)") (class "Default")
      (node (ref "J4") (pin "B8") (pinfunction "SBU2_B8") (pintype "passive+no_connect"))
    )
    (net (code "81") (name "unconnected-(U2-CBUS1-Pad14)") (class "Default")
      (node (ref "U2") (pin "14") (pinfunction "CBUS1_14") (pintype "passive+no_connect"))
    )
    (net (code "82") (name "unconnected-(U2-CBUS2-Pad7)") (class "Default")
      (node (ref "U2") (pin "7") (pinfunction "CBUS2_7") (pintype "passive+no_connect"))
    )
    (net (code "83") (name "unconnected-(U2-~{CTS}-Pad6)") (class "Default")
      (node (ref "U2") (pin "6") (pinfunction "~{CTS}_6") (pintype "passive+no_connect"))
    )
    (net (code "84") (name "unconnected-(U2-~{DCD}-Pad5)") (class "Default")
      (node (ref "U2") (pin "5") (pinfunction "~{DCD}_5") (pintype "passive+no_connect"))
    )
    (net (code "85") (name "unconnected-(U2-~{DSR}-Pad4)") (class "Default")
      (node (ref "U2") (pin "4") (pinfunction "~{DSR}_4") (pintype "passive+no_connect"))
    )
    (net (code "86") (name "unconnected-(U2-~{RI}-Pad2)") (class "Default")
      (node (ref "U2") (pin "2") (pinfunction "~{RI}_2") (pintype "passive+no_connect"))
    )
    (net (code "87") (name "unconnected-(U3-PG-Pad2)") (class "Default")
      (node (ref "U3") (pin "2") (pinfunction "PG_2") (pintype "passive+no_connect"))
    )
  )
)
